# Control_Board.net
KiCad netlist of a schematic drawn in Altium Designer
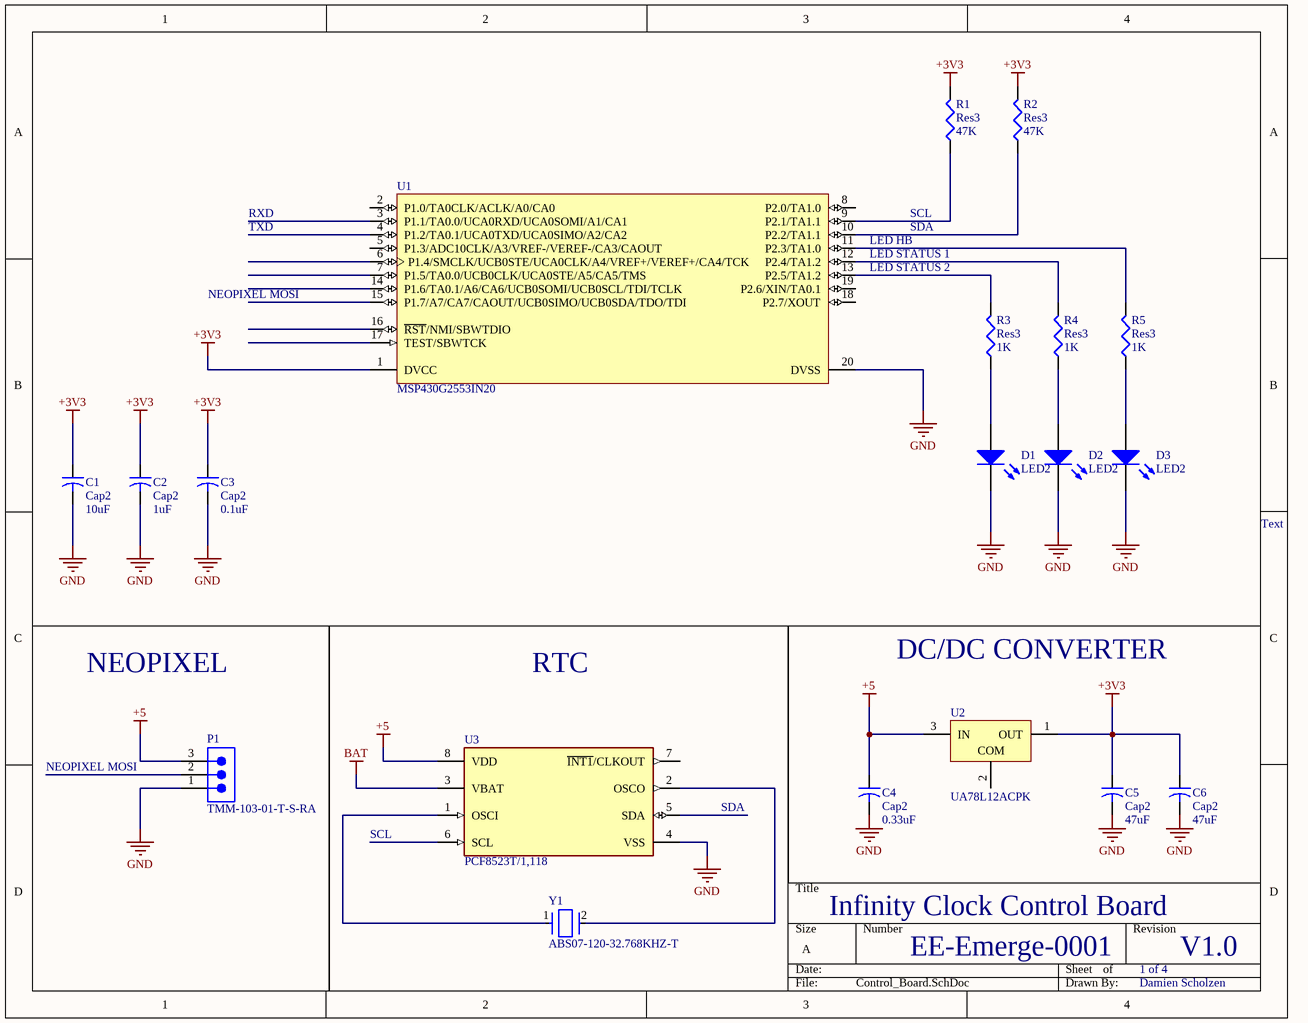
[diagram p0: Control_Board.SchDoc]

(export (version "E")
  (design (tool "Eeschema 10.0.6"))
  (components
    (comp (ref "C1")
      (value "Cap2")
      (footprint "C0805")
      (description "Capacitor")
      (fields (field (name "ALTIUM_VALUE") "10uF") (field (name "PUBLISHER") "Altium Limited"))
      (libsource (lib "EE_Emerge_SkillsProject (1)") (part "Cap2"))
    )
    (comp (ref "C2")
      (value "Cap2")
      (footprint "C0805")
      (description "Capacitor")
      (fields (field (name "ALTIUM_VALUE") "1uF") (field (name "PUBLISHER") "Altium Limited"))
      (libsource (lib "EE_Emerge_SkillsProject (1)") (part "Cap2_1"))
    )
    (comp (ref "C3")
      (value "Cap2")
      (footprint "C0805")
      (description "Capacitor")
      (fields (field (name "ALTIUM_VALUE") "0.1uF") (field (name "PUBLISHER") "Altium Limited"))
      (libsource (lib "EE_Emerge_SkillsProject (1)") (part "Cap2_2"))
    )
    (comp (ref "C4")
      (value "Cap2")
      (footprint "C0805")
      (description "Capacitor")
      (fields (field (name "ALTIUM_VALUE") "0.33uF") (field (name "PUBLISHER") "Altium Limited"))
      (libsource (lib "EE_Emerge_SkillsProject (1)") (part "Cap2_4"))
    )
    (comp (ref "C5")
      (value "Cap2")
      (footprint "C0805")
      (description "Capacitor")
      (fields (field (name "ALTIUM_VALUE") "47uF") (field (name "PUBLISHER") "Altium Limited"))
      (libsource (lib "EE_Emerge_SkillsProject (1)") (part "Cap2_5"))
    )
    (comp (ref "C6")
      (value "Cap2")
      (footprint "C0805")
      (description "Capacitor")
      (fields (field (name "ALTIUM_VALUE") "47uF") (field (name "PUBLISHER") "Altium Limited"))
      (libsource (lib "EE_Emerge_SkillsProject (1)") (part "Cap2_5"))
    )
    (comp (ref "D1")
      (value "LED2")
      (footprint "3.2X1.6X1.1")
      (description "Typical RED, GREEN, YELLOW, AMBER GaAs LED")
      (fields (field (name "PUBLISHER") "Altium Limited"))
      (libsource (lib "EE_Emerge_SkillsProject (1)") (part "LED2"))
    )
    (comp (ref "D2")
      (value "LED2")
      (footprint "3.2X1.6X1.1")
      (description "Typical RED, GREEN, YELLOW, AMBER GaAs LED")
      (fields (field (name "PUBLISHER") "Altium Limited"))
      (libsource (lib "EE_Emerge_SkillsProject (1)") (part "LED2"))
    )
    (comp (ref "D3")
      (value "LED2")
      (footprint "3.2X1.6X1.1")
      (description "Typical RED, GREEN, YELLOW, AMBER GaAs LED")
      (fields (field (name "PUBLISHER") "Altium Limited"))
      (libsource (lib "EE_Emerge_SkillsProject (1)") (part "LED2"))
    )
    (comp (ref "P1")
      (value "TMM-103-01-T-S-RA")
      (footprint "SMTC-TMM-103-01-X-S-RA")
      (description "Low Profile Through-Hole Header, Right Angle, -55 to 105 degC, 2 mm Pitch, 3-Pin, Male, RoHS")
      (fields (field (name "MANUFACTURER") "Samtec"))
      (libsource (lib "EE_Emerge_SkillsProject (1)") (part "CMP-1029-00176-1"))
    )
    (comp (ref "R1")
      (value "Res3")
      (footprint "6-0805_N")
      (description "Resistor")
      (fields (field (name "ALTIUM_VALUE") "47K") (field (name "PUBLISHER") "Altium Limited"))
      (libsource (lib "EE_Emerge_SkillsProject (1)") (part "Res3_1"))
    )
    (comp (ref "R2")
      (value "Res3")
      (footprint "6-0805_N")
      (description "Resistor")
      (fields (field (name "ALTIUM_VALUE") "47K") (field (name "PUBLISHER") "Altium Limited"))
      (libsource (lib "EE_Emerge_SkillsProject (1)") (part "Res3_1"))
    )
    (comp (ref "R3")
      (value "Res3")
      (footprint "6-0805_N")
      (description "Resistor")
      (fields (field (name "ALTIUM_VALUE") "1K") (field (name "PUBLISHER") "Altium Limited"))
      (libsource (lib "EE_Emerge_SkillsProject (1)") (part "Res3_2"))
    )
    (comp (ref "R4")
      (value "Res3")
      (footprint "6-0805_N")
      (description "Resistor")
      (fields (field (name "ALTIUM_VALUE") "1K") (field (name "PUBLISHER") "Altium Limited"))
      (libsource (lib "EE_Emerge_SkillsProject (1)") (part "Res3_2"))
    )
    (comp (ref "R5")
      (value "Res3")
      (footprint "6-0805_N")
      (description "Resistor")
      (fields (field (name "ALTIUM_VALUE") "1K") (field (name "PUBLISHER") "Altium Limited"))
      (libsource (lib "EE_Emerge_SkillsProject (1)") (part "Res3_2"))
    )
    (comp (ref "U1")
      (value "MSP430G2553IN20")
      (footprint "N0020A")
      (fields (field (name "MANUFACTURER") "Texas Instruments"))
      (libsource (lib "EE_Emerge_SkillsProject (1)") (part "CMP-0365-00184-2"))
    )
    (comp (ref "U2")
      (value "UA78L12ACPK")
      (footprint "PK0003A_M")
      (libsource (lib "EE_Emerge_SkillsProject (1)") (part "CMP-0324-00094-3"))
    )
    (comp (ref "U3")
      (value "PCF8523T/1,118")
      (footprint "FP-SOT96-1-IPC_B")
      (description "IC RTC CLK/CALENDAR I2C 8-SOIC")
      (libsource (lib "Altium Content Vault") (part "848ef7d52730a566ae52f9242454426"))
    )
    (comp (ref "Y1")
      (value "ABS07-120-32.768KHZ-T")
      (footprint "FP-ABS07-120-MFG")
      (description "CRYSTAL 32.7680KHZ 6PF SMD")
      (fields (field (name "TOLERANCE") "20ppm"))
      (libsource (lib "Altium Content Vault") (part "c23a69dc6c9e2f18f2079038eb95dd1"))
    )
  )
  (nets
    (net (code "1") (name "+3V3") (class "Default")
      (node (ref "C1") (pin "1") (pinfunction "1_1") (pintype "passive"))
      (node (ref "C2") (pin "1") (pinfunction "1_1") (pintype "passive"))
      (node (ref "C3") (pin "1") (pinfunction "1_1") (pintype "passive"))
      (node (ref "C5") (pin "1") (pinfunction "1_1") (pintype "passive"))
      (node (ref "C6") (pin "1") (pinfunction "1_1") (pintype "passive"))
      (node (ref "R1") (pin "2") (pinfunction "2_2") (pintype "passive"))
      (node (ref "R2") (pin "2") (pinfunction "2_2") (pintype "passive"))
      (node (ref "U1") (pin "1") (pinfunction "DVCC_1") (pintype "power_in"))
      (node (ref "U2") (pin "1") (pinfunction "OUT_1") (pintype "power_in"))
    )
    (net (code "2") (name "+5") (class "Default")
      (node (ref "C4") (pin "1") (pinfunction "1_1") (pintype "passive"))
      (node (ref "P1") (pin "3") (pinfunction "3_3") (pintype "passive"))
      (node (ref "U2") (pin "3") (pinfunction "IN_3") (pintype "power_in"))
      (node (ref "U3") (pin "8") (pinfunction "VDD_8") (pintype "power_in"))
    )
    (net (code "3") (name "BAT") (class "Default")
      (node (ref "U3") (pin "3") (pinfunction "VBAT_3") (pintype "power_in"))
    )
    (net (code "4") (name "GND") (class "Default")
      (node (ref "C1") (pin "2") (pinfunction "2_2") (pintype "passive"))
      (node (ref "C2") (pin "2") (pinfunction "2_2") (pintype "passive"))
      (node (ref "C3") (pin "2") (pinfunction "2_2") (pintype "passive"))
      (node (ref "C4") (pin "2") (pinfunction "2_2") (pintype "passive"))
      (node (ref "C5") (pin "2") (pinfunction "2_2") (pintype "passive"))
      (node (ref "C6") (pin "2") (pinfunction "2_2") (pintype "passive"))
      (node (ref "D1") (pin "2") (pinfunction "K_2") (pintype "passive"))
      (node (ref "D2") (pin "2") (pinfunction "K_2") (pintype "passive"))
      (node (ref "D3") (pin "2") (pinfunction "K_2") (pintype "passive"))
      (node (ref "P1") (pin "1") (pinfunction "1_1") (pintype "passive"))
      (node (ref "U1") (pin "20") (pinfunction "DVSS_20") (pintype "power_in"))
      (node (ref "U3") (pin "4") (pinfunction "VSS_4") (pintype "power_in"))
    )
    (net (code "5") (name "Net-(D1-A)") (class "Default")
      (node (ref "D1") (pin "1") (pinfunction "A_1") (pintype "passive"))
      (node (ref "R3") (pin "1") (pinfunction "1_1") (pintype "passive"))
    )
    (net (code "6") (name "Net-(D2-A)") (class "Default")
      (node (ref "D2") (pin "1") (pinfunction "A_1") (pintype "passive"))
      (node (ref "R4") (pin "1") (pinfunction "1_1") (pintype "passive"))
    )
    (net (code "7") (name "Net-(D3-A)") (class "Default")
      (node (ref "D3") (pin "1") (pinfunction "A_1") (pintype "passive"))
      (node (ref "R5") (pin "1") (pinfunction "1_1") (pintype "passive"))
    )
    (net (code "8") (name "Net-(U1-P2.1{slash}TA1.1)") (class "Default")
      (node (ref "R1") (pin "1") (pinfunction "1_1") (pintype "passive"))
      (node (ref "U1") (pin "9") (pinfunction "P2.1/TA1.1_9") (pintype "bidirectional"))
    )
    (net (code "9") (name "Net-(U1-P2.2{slash}TA1.1)") (class "Default")
      (node (ref "R2") (pin "1") (pinfunction "1_1") (pintype "passive"))
      (node (ref "U1") (pin "10") (pinfunction "P2.2/TA1.1_10") (pintype "bidirectional"))
    )
    (net (code "10") (name "Net-(U1-P2.3{slash}TA1.0)") (class "Default")
      (node (ref "R5") (pin "2") (pinfunction "2_2") (pintype "passive"))
      (node (ref "U1") (pin "11") (pinfunction "P2.3/TA1.0_11") (pintype "bidirectional"))
    )
    (net (code "11") (name "Net-(U1-P2.4{slash}TA1.2)") (class "Default")
      (node (ref "R4") (pin "2") (pinfunction "2_2") (pintype "passive"))
      (node (ref "U1") (pin "12") (pinfunction "P2.4/TA1.2_12") (pintype "bidirectional"))
    )
    (net (code "12") (name "Net-(U1-P2.5{slash}TA1.2)") (class "Default")
      (node (ref "R3") (pin "2") (pinfunction "2_2") (pintype "passive"))
      (node (ref "U1") (pin "13") (pinfunction "P2.5/TA1.2_13") (pintype "bidirectional"))
    )
    (net (code "13") (name "Net-(U3-OSCI)") (class "Default")
      (node (ref "U3") (pin "1") (pinfunction "OSCI_1") (pintype "input"))
      (node (ref "Y1") (pin "1") (pinfunction "1_1") (pintype "passive"))
    )
    (net (code "14") (name "Net-(U3-OSCO)") (class "Default")
      (node (ref "U3") (pin "2") (pinfunction "OSCO_2") (pintype "output"))
      (node (ref "Y1") (pin "2") (pinfunction "2_2") (pintype "passive"))
    )
    (net (code "15") (name "unconnected-(P1-Pad2)") (class "Default")
      (node (ref "P1") (pin "2") (pinfunction "2_2") (pintype "passive"))
    )
    (net (code "16") (name "unconnected-(U1-P1.0{slash}TA0CLK{slash}ACLK{slash}A0{slash}CA0-Pad2)") (class "Default")
      (node (ref "U1") (pin "2") (pinfunction "P1.0/TA0CLK/ACLK/A0/CA0_2") (pintype "bidirectional"))
    )
    (net (code "17") (name "unconnected-(U1-P1.1{slash}TA0.0{slash}UCA0RXD{slash}UCA0SOMI{slash}A1{slash}CA1-Pad3)") (class "Default")
      (node (ref "U1") (pin "3") (pinfunction "P1.1/TA0.0/UCA0RXD/UCA0SOMI/A1/CA1_3") (pintype "bidirectional"))
    )
    (net (code "18") (name "unconnected-(U1-P1.2{slash}TA0.1{slash}UCA0TXD{slash}UCA0SIMO{slash}A2{slash}CA2-Pad4)") (class "Default")
      (node (ref "U1") (pin "4") (pinfunction "P1.2/TA0.1/UCA0TXD/UCA0SIMO/A2/CA2_4") (pintype "bidirectional"))
    )
    (net (code "19") (name "unconnected-(U1-P1.3{slash}ADC10CLK{slash}A3{slash}VREF-{slash}VEREF-{slash}CA3{slash}CAOUT-Pad5)") (class "Default")
      (node (ref "U1") (pin "5") (pinfunction "P1.3/ADC10CLK/A3/VREF-/VEREF-/CA3/CAOUT_5") (pintype "bidirectional"))
    )
    (net (code "20") (name "unconnected-(U1-P1.4{slash}SMCLK{slash}UCB0STE{slash}UCA0CLK{slash}A4{slash}VREF+{slash}VEREF+{slash}CA4{slash}TCK-Pad6)") (class "Default")
      (node (ref "U1") (pin "6") (pinfunction "P1.4/SMCLK/UCB0STE/UCA0CLK/A4/VREF+/VEREF+/CA4/TCK_6") (pintype "bidirectional"))
    )
    (net (code "21") (name "unconnected-(U1-P1.5{slash}TA0.0{slash}UCB0CLK{slash}UCA0STE{slash}A5{slash}CA5{slash}TMS-Pad7)") (class "Default")
      (node (ref "U1") (pin "7") (pinfunction "P1.5/TA0.0/UCB0CLK/UCA0STE/A5/CA5/TMS_7") (pintype "bidirectional"))
    )
    (net (code "22") (name "unconnected-(U1-P1.6{slash}TA0.1{slash}A6{slash}CA6{slash}UCB0SOMI{slash}UCB0SCL{slash}TDI{slash}TCLK-Pad14)") (class "Default")
      (node (ref "U1") (pin "14") (pinfunction "P1.6/TA0.1/A6/CA6/UCB0SOMI/UCB0SCL/TDI/TCLK_14") (pintype "bidirectional"))
    )
    (net (code "23") (name "unconnected-(U1-P1.7{slash}A7{slash}CA7{slash}CAOUT{slash}UCB0SIMO{slash}UCB0SDA{slash}TDO{slash}TDI-Pad15)") (class "Default")
      (node (ref "U1") (pin "15") (pinfunction "P1.7/A7/CA7/CAOUT/UCB0SIMO/UCB0SDA/TDO/TDI_15") (pintype "bidirectional"))
    )
    (net (code "24") (name "unconnected-(U1-P2.0{slash}TA1.0-Pad8)") (class "Default")
      (node (ref "U1") (pin "8") (pinfunction "P2.0/TA1.0_8") (pintype "bidirectional"))
    )
    (net (code "25") (name "unconnected-(U1-P2.6{slash}XIN{slash}TA0.1-Pad19)") (class "Default")
      (node (ref "U1") (pin "19") (pinfunction "P2.6/XIN/TA0.1_19") (pintype "bidirectional"))
    )
    (net (code "26") (name "unconnected-(U1-P2.7{slash}XOUT-Pad18)") (class "Default")
      (node (ref "U1") (pin "18") (pinfunction "P2.7/XOUT_18") (pintype "bidirectional"))
    )
    (net (code "27") (name "unconnected-(U1-TEST{slash}SBWTCK-Pad17)") (class "Default")
      (node (ref "U1") (pin "17") (pinfunction "TEST/SBWTCK_17") (pintype "input"))
    )
    (net (code "28") (name "unconnected-(U1-~{RST}{slash}NMI{slash}SBWTDIO-Pad16)") (class "Default")
      (node (ref "U1") (pin "16") (pinfunction "~{RST}/NMI/SBWTDIO_16") (pintype "bidirectional"))
    )
    (net (code "29") (name "unconnected-(U2-COM-Pad2)") (class "Default")
      (node (ref "U2") (pin "2") (pinfunction "COM_2") (pintype "power_in"))
    )
    (net (code "30") (name "unconnected-(U3-SCL-Pad6)") (class "Default")
      (node (ref "U3") (pin "6") (pinfunction "SCL_6") (pintype "input"))
    )
    (net (code "31") (name "unconnected-(U3-SDA-Pad5)") (class "Default")
      (node (ref "U3") (pin "5") (pinfunction "SDA_5") (pintype "bidirectional"))
    )
    (net (code "32") (name "unconnected-(U3-~{INT1}{slash}CLKOUT-Pad7)") (class "Default")
      (node (ref "U3") (pin "7") (pinfunction "~{INT1}/CLKOUT_7") (pintype "output"))
    )
  )
)
